# HKCitVDR_PCB.net
KiCad netlist of a schematic drawn in Altium Designer
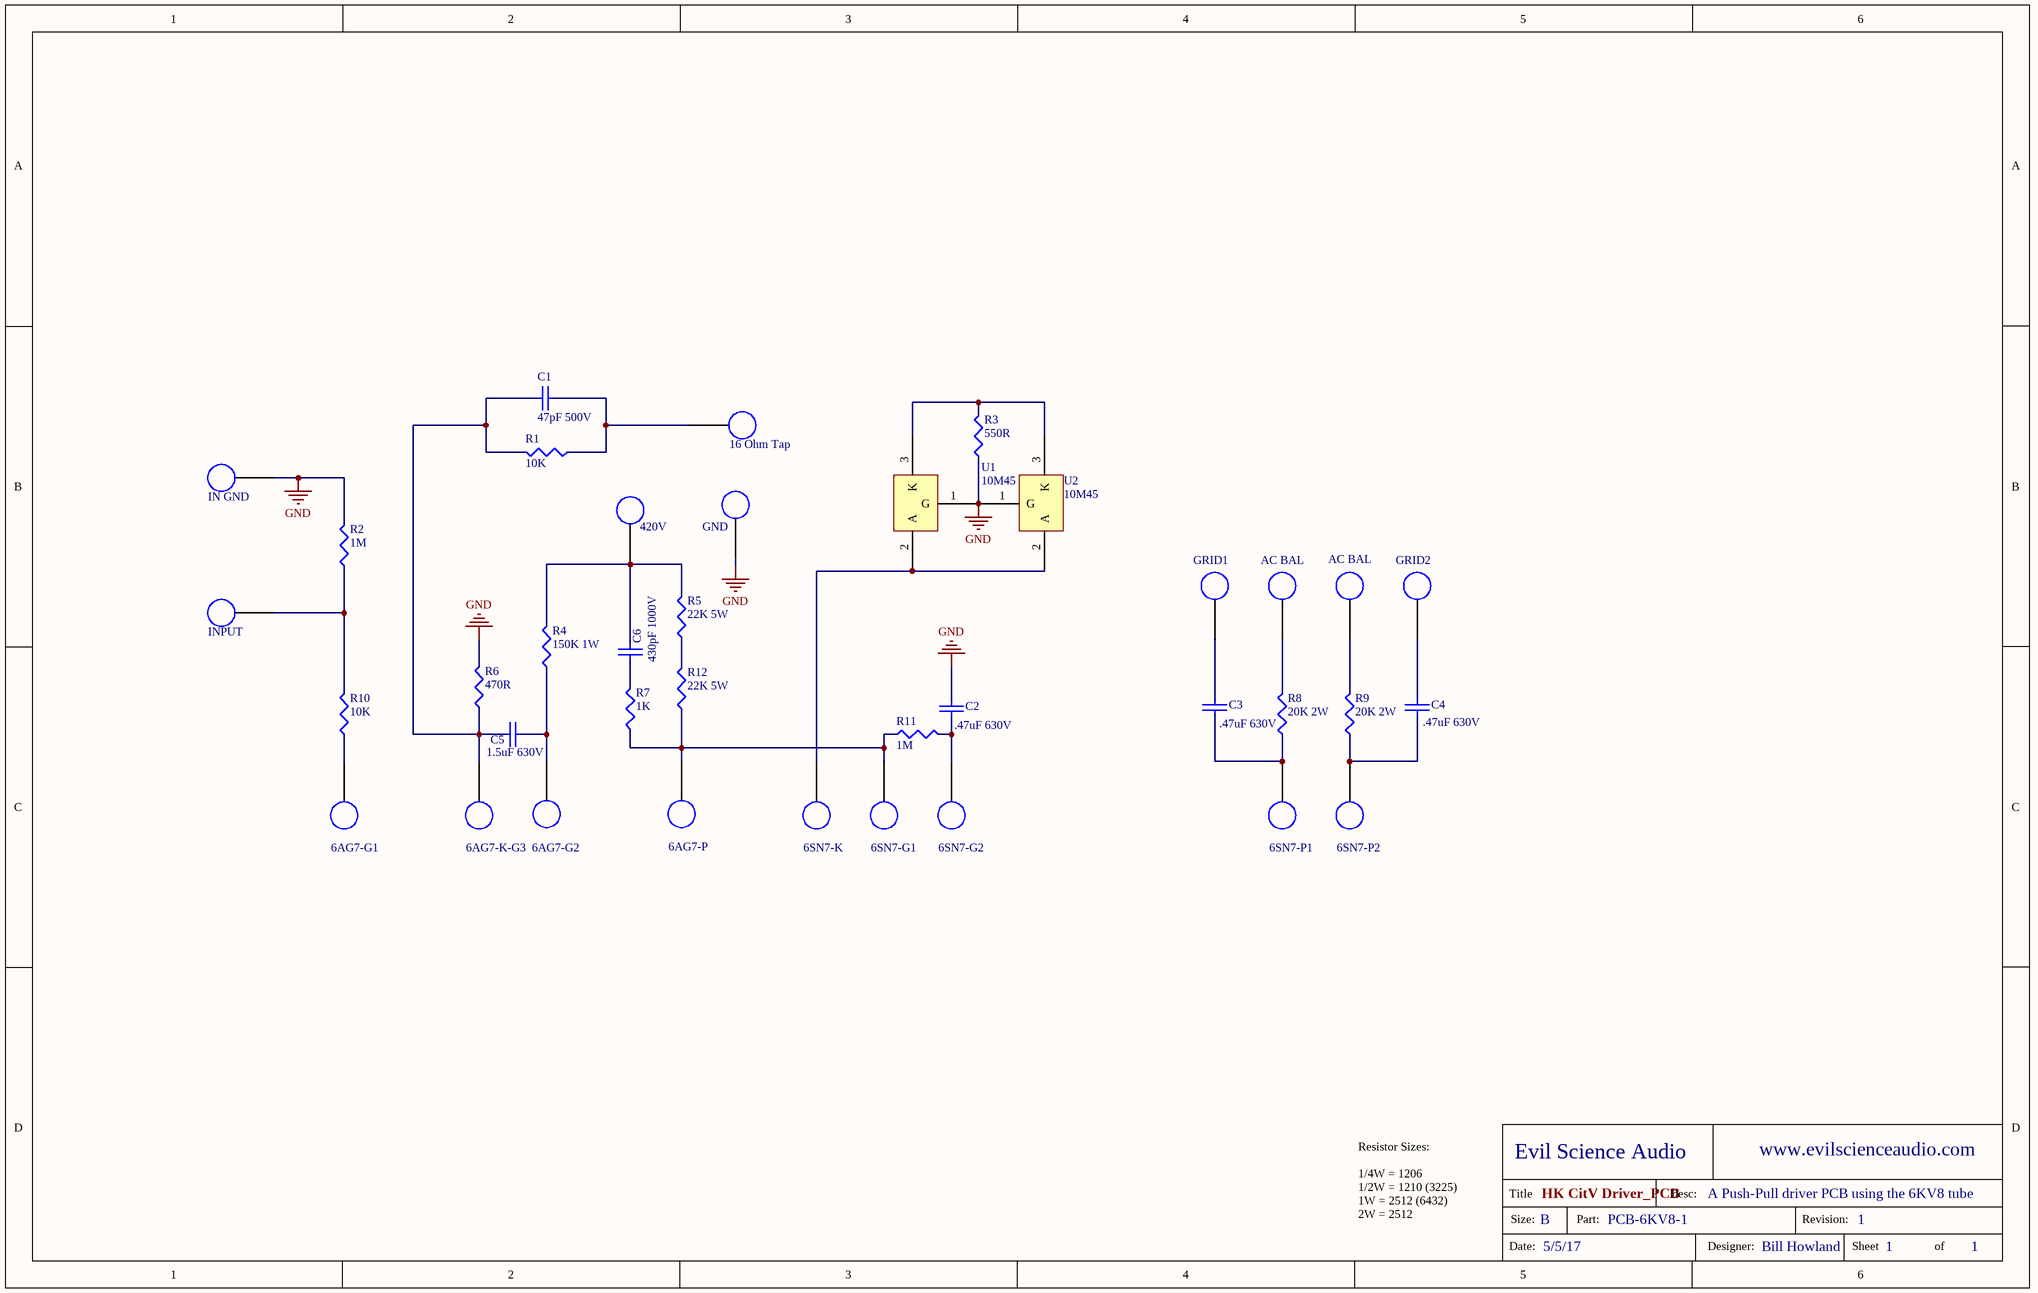
[diagram p0: HKCitVDR_PCB.SchDoc]

(export (version "E")
  (design (tool "Eeschema 10.0.6"))
  (components
    (comp (ref "C1")
      (value "47pF 500V")
      (footprint "CDE 47PF MICA")
      (description "Capacitor")
      (fields (field (name "MFG PART NUM") "C3216X7R1H474K"))
      (libsource (lib "Bills") (part "CAP_6"))
    )
    (comp (ref "C2")
      (value ".47uF 630V")
      (footprint "SOLEN .47/630")
      (description "Capacitor")
      (fields (field (name "MFG PART NUM") "C3216X7R1H474K"))
      (libsource (lib "Bills") (part "CAP_6"))
    )
    (comp (ref "C3")
      (value ".47uF 630V")
      (footprint "SOLEN .47/630")
      (description "Capacitor")
      (fields (field (name "MFG PART NUM") "C3216X7R1H474K"))
      (libsource (lib "Bills") (part "CAP_6"))
    )
    (comp (ref "C4")
      (value ".47uF 630V")
      (footprint "SOLEN .47/630")
      (description "Capacitor")
      (fields (field (name "MFG PART NUM") "C3216X7R1H474K"))
      (libsource (lib "Bills") (part "CAP_6"))
    )
    (comp (ref "C5")
      (value "1.5uF 630V")
      (footprint "SOLEN 1.5/630")
      (description "Capacitor")
      (fields (field (name "MFG PART NUM") "C3216X7R1H474K"))
      (libsource (lib "Bills") (part "CAP_6"))
    )
    (comp (ref "C6")
      (value "430pF 1000V")
      (footprint "CDE 430PF MICA")
      (description "Capacitor")
      (fields (field (name "MFG PART NUM") "C3216X7R1H474K"))
      (libsource (lib "Bills") (part "CAP_6"))
    )
    (comp (ref "R1")
      (value "10K")
      (footprint "RES 1/4W THRU_HOLE")
      (libsource (lib "Bills") (part "RES_THRU"))
    )
    (comp (ref "R2")
      (value "1M")
      (footprint "RES 1/4W THRU_HOLE")
      (libsource (lib "Bills") (part "RES_THRU"))
    )
    (comp (ref "R3")
      (value "550R")
      (footprint "RES 1/4W THRU_HOLE")
      (libsource (lib "Bills") (part "RES_THRU"))
    )
    (comp (ref "R4")
      (value "150K 1W")
      (footprint "RES 1W THRU_HOLE")
      (libsource (lib "Bills") (part "RES_THRU"))
    )
    (comp (ref "R5")
      (value "22K 5W")
      (footprint "RES 5W THRU_HOLE")
      (libsource (lib "Bills") (part "RES_THRU"))
    )
    (comp (ref "R6")
      (value "470R")
      (footprint "RES 1/4W THRU_HOLE")
      (libsource (lib "Bills") (part "RES_THRU"))
    )
    (comp (ref "R7")
      (value "1K")
      (footprint "RES 1/4W THRU_HOLE")
      (libsource (lib "Bills") (part "RES_THRU"))
    )
    (comp (ref "R8")
      (value "20K 2W")
      (footprint "RES 2W THRU_HOLE")
      (libsource (lib "Bills") (part "RES_THRU"))
    )
    (comp (ref "R9")
      (value "20K 2W")
      (footprint "RES 2W THRU_HOLE")
      (libsource (lib "Bills") (part "RES_THRU"))
    )
    (comp (ref "R10")
      (value "10K")
      (footprint "RES 1/4W THRU_HOLE")
      (libsource (lib "Bills") (part "RES_THRU"))
    )
    (comp (ref "R11")
      (value "1M")
      (footprint "RES 1/4W THRU_HOLE")
      (libsource (lib "Bills") (part "RES_THRU"))
    )
    (comp (ref "R12")
      (value "22K 5W")
      (footprint "RES 5W THRU_HOLE")
      (libsource (lib "Bills") (part "RES_THRU"))
    )
    (comp (ref "TP1")
      (value "16 Ohm Tap")
      (footprint "Test_Point")
      (libsource (lib "Bills") (part "Test_Point1"))
    )
    (comp (ref "TP2") (value "INPUT") (footprint "Test_Point") (libsource (lib "Bills") (part "Test_Point1")))
    (comp (ref "TP3")
      (value "IN GND")
      (footprint "Test_Point")
      (libsource (lib "Bills") (part "Test_Point1"))
    )
    (comp (ref "TP4") (value "GRID1") (footprint "Test_Point") (libsource (lib "Bills") (part "Test_Point1")))
    (comp (ref "TP5")
      (value "AC BAL")
      (footprint "Test_Point")
      (libsource (lib "Bills") (part "Test_Point1"))
    )
    (comp (ref "TP6")
      (value "AC BAL")
      (footprint "Test_Point")
      (libsource (lib "Bills") (part "Test_Point1"))
    )
    (comp (ref "TP7") (value "GRID2") (footprint "Test_Point") (libsource (lib "Bills") (part "Test_Point1")))
    (comp (ref "TP8")
      (value "6AG7-G1")
      (footprint "Test_Point")
      (libsource (lib "Bills") (part "Test_Point1"))
    )
    (comp (ref "TP9")
      (value "6AG7-K-G3")
      (footprint "Test_Point")
      (libsource (lib "Bills") (part "Test_Point1"))
    )
    (comp (ref "TP10")
      (value "6AG7-G2")
      (footprint "Test_Point")
      (libsource (lib "Bills") (part "Test_Point1"))
    )
    (comp (ref "TP11") (value "GND") (footprint "Test_Point") (libsource (lib "Bills") (part "Test_Point1")))
    (comp (ref "TP12")
      (value "6AG7-P")
      (footprint "Test_Point")
      (libsource (lib "Bills") (part "Test_Point1"))
    )
    (comp (ref "TP13")
      (value "6SN7-K")
      (footprint "Test_Point")
      (libsource (lib "Bills") (part "Test_Point1"))
    )
    (comp (ref "TP14")
      (value "6SN7-G1")
      (footprint "Test_Point")
      (libsource (lib "Bills") (part "Test_Point1"))
    )
    (comp (ref "TP15")
      (value "6SN7-G2")
      (footprint "Test_Point")
      (libsource (lib "Bills") (part "Test_Point1"))
    )
    (comp (ref "TP16")
      (value "6SN7-P1")
      (footprint "Test_Point")
      (libsource (lib "Bills") (part "Test_Point1"))
    )
    (comp (ref "TP17")
      (value "6SN7-P2")
      (footprint "Test_Point")
      (libsource (lib "Bills") (part "Test_Point1"))
    )
    (comp (ref "TP18") (value "420V") (footprint "Test_Point") (libsource (lib "Bills") (part "Test_Point1")))
    (comp (ref "U1") (value "10M45") (footprint "TO-252AA") (libsource (lib "") (part "10M45_1")))
    (comp (ref "U2") (value "10M45") (footprint "TO-252AA") (libsource (lib "Bills") (part "10M45")))
  )
  (nets
    (net (code "1") (name "GND") (class "Default")
      (node (ref "C2") (pin "2") (pinfunction "2_2") (pintype "passive"))
      (node (ref "R2") (pin "2") (pinfunction "2_2") (pintype "passive"))
      (node (ref "R3") (pin "1") (pinfunction "1_1") (pintype "passive"))
      (node (ref "R6") (pin "2") (pinfunction "2_2") (pintype "passive"))
      (node (ref "TP11") (pin "1") (pinfunction "1_1") (pintype "passive"))
      (node (ref "TP3") (pin "1") (pinfunction "1_1") (pintype "passive"))
      (node (ref "U1") (pin "1") (pinfunction "G_1") (pintype "passive"))
      (node (ref "U2") (pin "1") (pinfunction "G_1") (pintype "passive"))
    )
    (net (code "2") (name "Net-(C1-Pad1)") (class "Default")
      (node (ref "C1") (pin "1") (pinfunction "1_1") (pintype "passive"))
      (node (ref "C5") (pin "1") (pinfunction "1_1") (pintype "passive"))
      (node (ref "R1") (pin "2") (pinfunction "2_2") (pintype "passive"))
      (node (ref "R6") (pin "1") (pinfunction "1_1") (pintype "passive"))
      (node (ref "TP9") (pin "1") (pinfunction "1_1") (pintype "passive"))
    )
    (net (code "3") (name "Net-(C1-Pad2)") (class "Default")
      (node (ref "C1") (pin "2") (pinfunction "2_2") (pintype "passive"))
      (node (ref "R1") (pin "1") (pinfunction "1_1") (pintype "passive"))
      (node (ref "TP1") (pin "1") (pinfunction "1_1") (pintype "passive"))
    )
    (net (code "4") (name "Net-(C2-Pad1)") (class "Default")
      (node (ref "C2") (pin "1") (pinfunction "1_1") (pintype "passive"))
      (node (ref "R11") (pin "2") (pinfunction "2_2") (pintype "passive"))
      (node (ref "TP15") (pin "1") (pinfunction "1_1") (pintype "passive"))
    )
    (net (code "5") (name "Net-(C3-Pad1)") (class "Default")
      (node (ref "C3") (pin "1") (pinfunction "1_1") (pintype "passive"))
      (node (ref "R8") (pin "1") (pinfunction "1_1") (pintype "passive"))
      (node (ref "TP16") (pin "1") (pinfunction "1_1") (pintype "passive"))
    )
    (net (code "6") (name "Net-(C3-Pad2)") (class "Default")
      (node (ref "C3") (pin "2") (pinfunction "2_2") (pintype "passive"))
      (node (ref "TP4") (pin "1") (pinfunction "1_1") (pintype "passive"))
    )
    (net (code "7") (name "Net-(C4-Pad1)") (class "Default")
      (node (ref "C4") (pin "1") (pinfunction "1_1") (pintype "passive"))
      (node (ref "R9") (pin "1") (pinfunction "1_1") (pintype "passive"))
      (node (ref "TP17") (pin "1") (pinfunction "1_1") (pintype "passive"))
    )
    (net (code "8") (name "Net-(C4-Pad2)") (class "Default")
      (node (ref "C4") (pin "2") (pinfunction "2_2") (pintype "passive"))
      (node (ref "TP7") (pin "1") (pinfunction "1_1") (pintype "passive"))
    )
    (net (code "9") (name "Net-(C5-Pad2)") (class "Default")
      (node (ref "C5") (pin "2") (pinfunction "2_2") (pintype "passive"))
      (node (ref "R4") (pin "1") (pinfunction "1_1") (pintype "passive"))
      (node (ref "TP10") (pin "1") (pinfunction "1_1") (pintype "passive"))
    )
    (net (code "10") (name "Net-(C6-Pad1)") (class "Default")
      (node (ref "C6") (pin "1") (pinfunction "1_1") (pintype "passive"))
      (node (ref "R4") (pin "2") (pinfunction "2_2") (pintype "passive"))
      (node (ref "R5") (pin "2") (pinfunction "2_2") (pintype "passive"))
      (node (ref "TP18") (pin "1") (pinfunction "1_1") (pintype "passive"))
    )
    (net (code "11") (name "Net-(C6-Pad2)") (class "Default")
      (node (ref "C6") (pin "2") (pinfunction "2_2") (pintype "passive"))
      (node (ref "R7") (pin "2") (pinfunction "2_2") (pintype "passive"))
    )
    (net (code "12") (name "Net-(R8-Pad2)") (class "Default")
      (node (ref "R8") (pin "2") (pinfunction "2_2") (pintype "passive"))
      (node (ref "TP5") (pin "1") (pinfunction "1_1") (pintype "passive"))
    )
    (net (code "13") (name "Net-(R9-Pad2)") (class "Default")
      (node (ref "R9") (pin "2") (pinfunction "2_2") (pintype "passive"))
      (node (ref "TP6") (pin "1") (pinfunction "1_1") (pintype "passive"))
    )
    (net (code "14") (name "Net-(R10-Pad1)") (class "Default")
      (node (ref "R10") (pin "1") (pinfunction "1_1") (pintype "passive"))
      (node (ref "TP8") (pin "1") (pinfunction "1_1") (pintype "passive"))
    )
    (net (code "15") (name "Net-(R10-Pad2)") (class "Default")
      (node (ref "R10") (pin "2") (pinfunction "2_2") (pintype "passive"))
      (node (ref "R2") (pin "1") (pinfunction "1_1") (pintype "passive"))
      (node (ref "TP2") (pin "1") (pinfunction "1_1") (pintype "passive"))
    )
    (net (code "16") (name "Net-(R11-Pad1)") (class "Default")
      (node (ref "R11") (pin "1") (pinfunction "1_1") (pintype "passive"))
      (node (ref "R12") (pin "1") (pinfunction "1_1") (pintype "passive"))
      (node (ref "R7") (pin "1") (pinfunction "1_1") (pintype "passive"))
      (node (ref "TP12") (pin "1") (pinfunction "1_1") (pintype "passive"))
      (node (ref "TP14") (pin "1") (pinfunction "1_1") (pintype "passive"))
    )
    (net (code "17") (name "Net-(R12-Pad2)") (class "Default")
      (node (ref "R12") (pin "2") (pinfunction "2_2") (pintype "passive"))
      (node (ref "R5") (pin "1") (pinfunction "1_1") (pintype "passive"))
    )
    (net (code "18") (name "Net-(U1-A)") (class "Default")
      (node (ref "TP13") (pin "1") (pinfunction "1_1") (pintype "passive"))
      (node (ref "U1") (pin "2") (pinfunction "A_2") (pintype "passive"))
      (node (ref "U2") (pin "2") (pinfunction "A_2") (pintype "passive"))
    )
    (net (code "19") (name "Net-(U1-K)") (class "Default")
      (node (ref "R3") (pin "2") (pinfunction "2_2") (pintype "passive"))
      (node (ref "U1") (pin "3") (pinfunction "K_3") (pintype "passive"))
      (node (ref "U2") (pin "3") (pinfunction "K_3") (pintype "passive"))
    )
  )
)
